# Power.net
KiCad netlist of a schematic drawn in Altium Designer
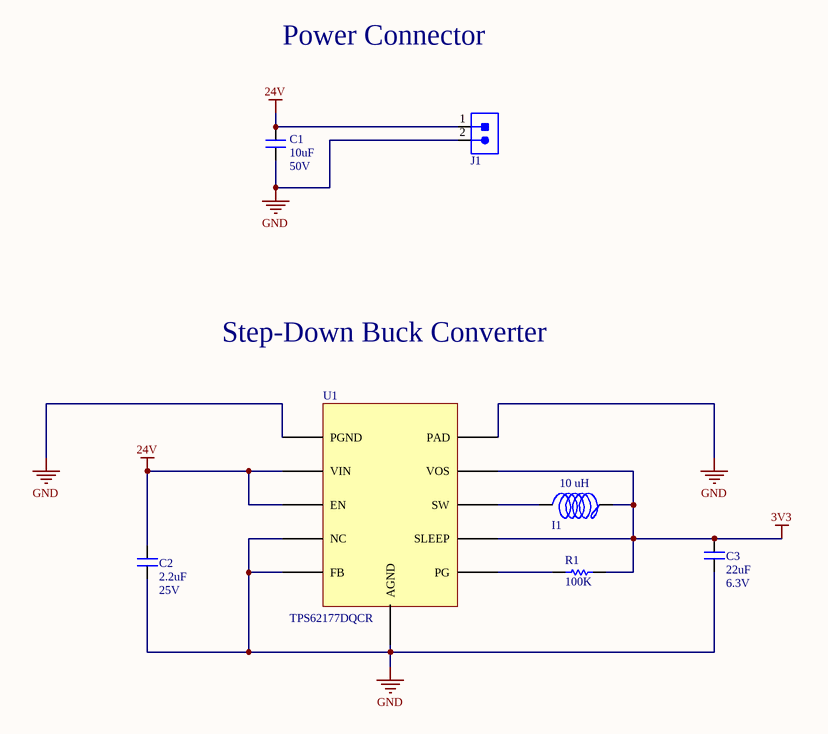
[diagram p0: Power.SchDoc]

(export (version "E")
  (design (tool "Eeschema 10.0.6"))
  (components
    (comp (ref "C1")
      (value "10uF")
      (footprint "CAPC1206(3216)")
      (description "CAP CER 10UF 50V X5R 1206")
      (fields (field (name "VOLTAGE RATING") "50V"))
      (libsource (lib "UWRT_Schematic_Library_2020") (part "CAP_10uF_50V_1206"))
    )
    (comp (ref "C2")
      (value "2.2uF")
      (footprint "CAPC2012X140N")
      (description "CAP CER 2.2UF 25V X7R 0805")
      (fields
        (field (name "TOLERANCE") "10%")
        (field (name "VOLTAGE RATING") "25V")
        (field (name "Comment") "CAP_2.2uF_25V_0805")
      )
      (libsource (lib "UWRT_Schematic_Library_2020") (part "CAP_2.2uF_25V_0805"))
    )
    (comp (ref "C3")
      (value "22uF")
      (footprint "CAPC0603(1608)55_N")
      (description "CAP CER 22UF 6.3V X5R 0805")
      (fields
        (field (name "TOLERANCE") "20%")
        (field (name "VOLTAGE RATING") "6.3V")
        (field (name "Comment") "CAP_22uF_6.3V_0805")
      )
      (libsource (lib "UWRT_Schematic_Library_2020") (part "CAP_22uF_6.3V_0805"))
    )
    (comp (ref "I1")
      (value "IND_10uH_6045")
      (footprint "IND_BOURNS_SRN6045")
      (description "IND WIRE 10 UH 6045")
      (libsource (lib "UWRT_Schematic_Library_2020") (part "IND_10uH_6045"))
    )
    (comp (ref "J1")
      (value "CON_2M_TERM")
      (footprint "1935161")
      (description "TERM BLK 2POS SIDE ENTRY 5MM")
      (fields (field (name "VOLTAGE") "300V"))
      (libsource (lib "UWRT_Schematic_Library_2020") (part "CON_2M_TERM"))
    )
    (comp (ref "R1")
      (value "100K")
      (footprint "RESC0603(1608)_N")
      (description "RES SMD 100K OHM 5% 1/10W 0603")
      (fields (field (name "TOLERANCE") "5%") (field (name "Comment") "RES_100K_0603"))
      (libsource (lib "UWRT_Schematic_Library_2020") (part "RES_100K_0603"))
    )
    (comp (ref "U1")
      (value "TPS62177DQCR")
      (footprint "DQC0010A")
      (description "IC REG BUCK 3.3V 500MA 10WSON")
      (libsource (lib "UWRT_Schematic_Library_2020") (part "TPS62177DQCR"))
    )
  )
  (nets
    (net (code "1") (name "3V3") (class "Default")
      (node (ref "C3") (pin "2") (pinfunction "2_2") (pintype "passive"))
      (node (ref "I1") (pin "1") (pinfunction "1_1") (pintype "passive"))
      (node (ref "R1") (pin "1") (pinfunction "1_1") (pintype "passive"))
      (node (ref "U1") (pin "10") (pinfunction "VOS_10") (pintype "passive"))
      (node (ref "U1") (pin "8") (pinfunction "SLEEP_8") (pintype "passive"))
    )
    (net (code "2") (name "24V") (class "Default")
      (node (ref "C1") (pin "2") (pinfunction "2_2") (pintype "passive"))
      (node (ref "C2") (pin "2") (pinfunction "2_2") (pintype "passive"))
      (node (ref "J1") (pin "1") (pinfunction "1_1") (pintype "passive"))
      (node (ref "U1") (pin "2") (pinfunction "VIN_2") (pintype "passive"))
      (node (ref "U1") (pin "3") (pinfunction "EN_3") (pintype "passive"))
    )
    (net (code "3") (name "GND") (class "Default")
      (node (ref "C1") (pin "1") (pinfunction "1_1") (pintype "passive"))
      (node (ref "C2") (pin "1") (pinfunction "1_1") (pintype "passive"))
      (node (ref "C3") (pin "1") (pinfunction "1_1") (pintype "passive"))
      (node (ref "J1") (pin "2") (pinfunction "2_2") (pintype "passive"))
      (node (ref "U1") (pin "1") (pinfunction "PGND_1") (pintype "passive"))
      (node (ref "U1") (pin "11") (pinfunction "PAD_11") (pintype "passive"))
      (node (ref "U1") (pin "4") (pinfunction "NC_4") (pintype "passive"))
      (node (ref "U1") (pin "5") (pinfunction "FB_5") (pintype "passive"))
      (node (ref "U1") (pin "6") (pinfunction "AGND_6") (pintype "passive"))
    )
    (net (code "4") (name "Net-(U1-PG)") (class "Default")
      (node (ref "R1") (pin "2") (pinfunction "2_2") (pintype "passive"))
      (node (ref "U1") (pin "7") (pinfunction "PG_7") (pintype "passive"))
    )
    (net (code "5") (name "Net-(U1-SW)") (class "Default")
      (node (ref "I1") (pin "1") (pinfunction "1_1") (pintype "passive"))
      (node (ref "U1") (pin "9") (pinfunction "SW_9") (pintype "passive"))
    )
  )
)
